# stoveguard.net
KiCad netlist of a schematic drawn in EAGLE
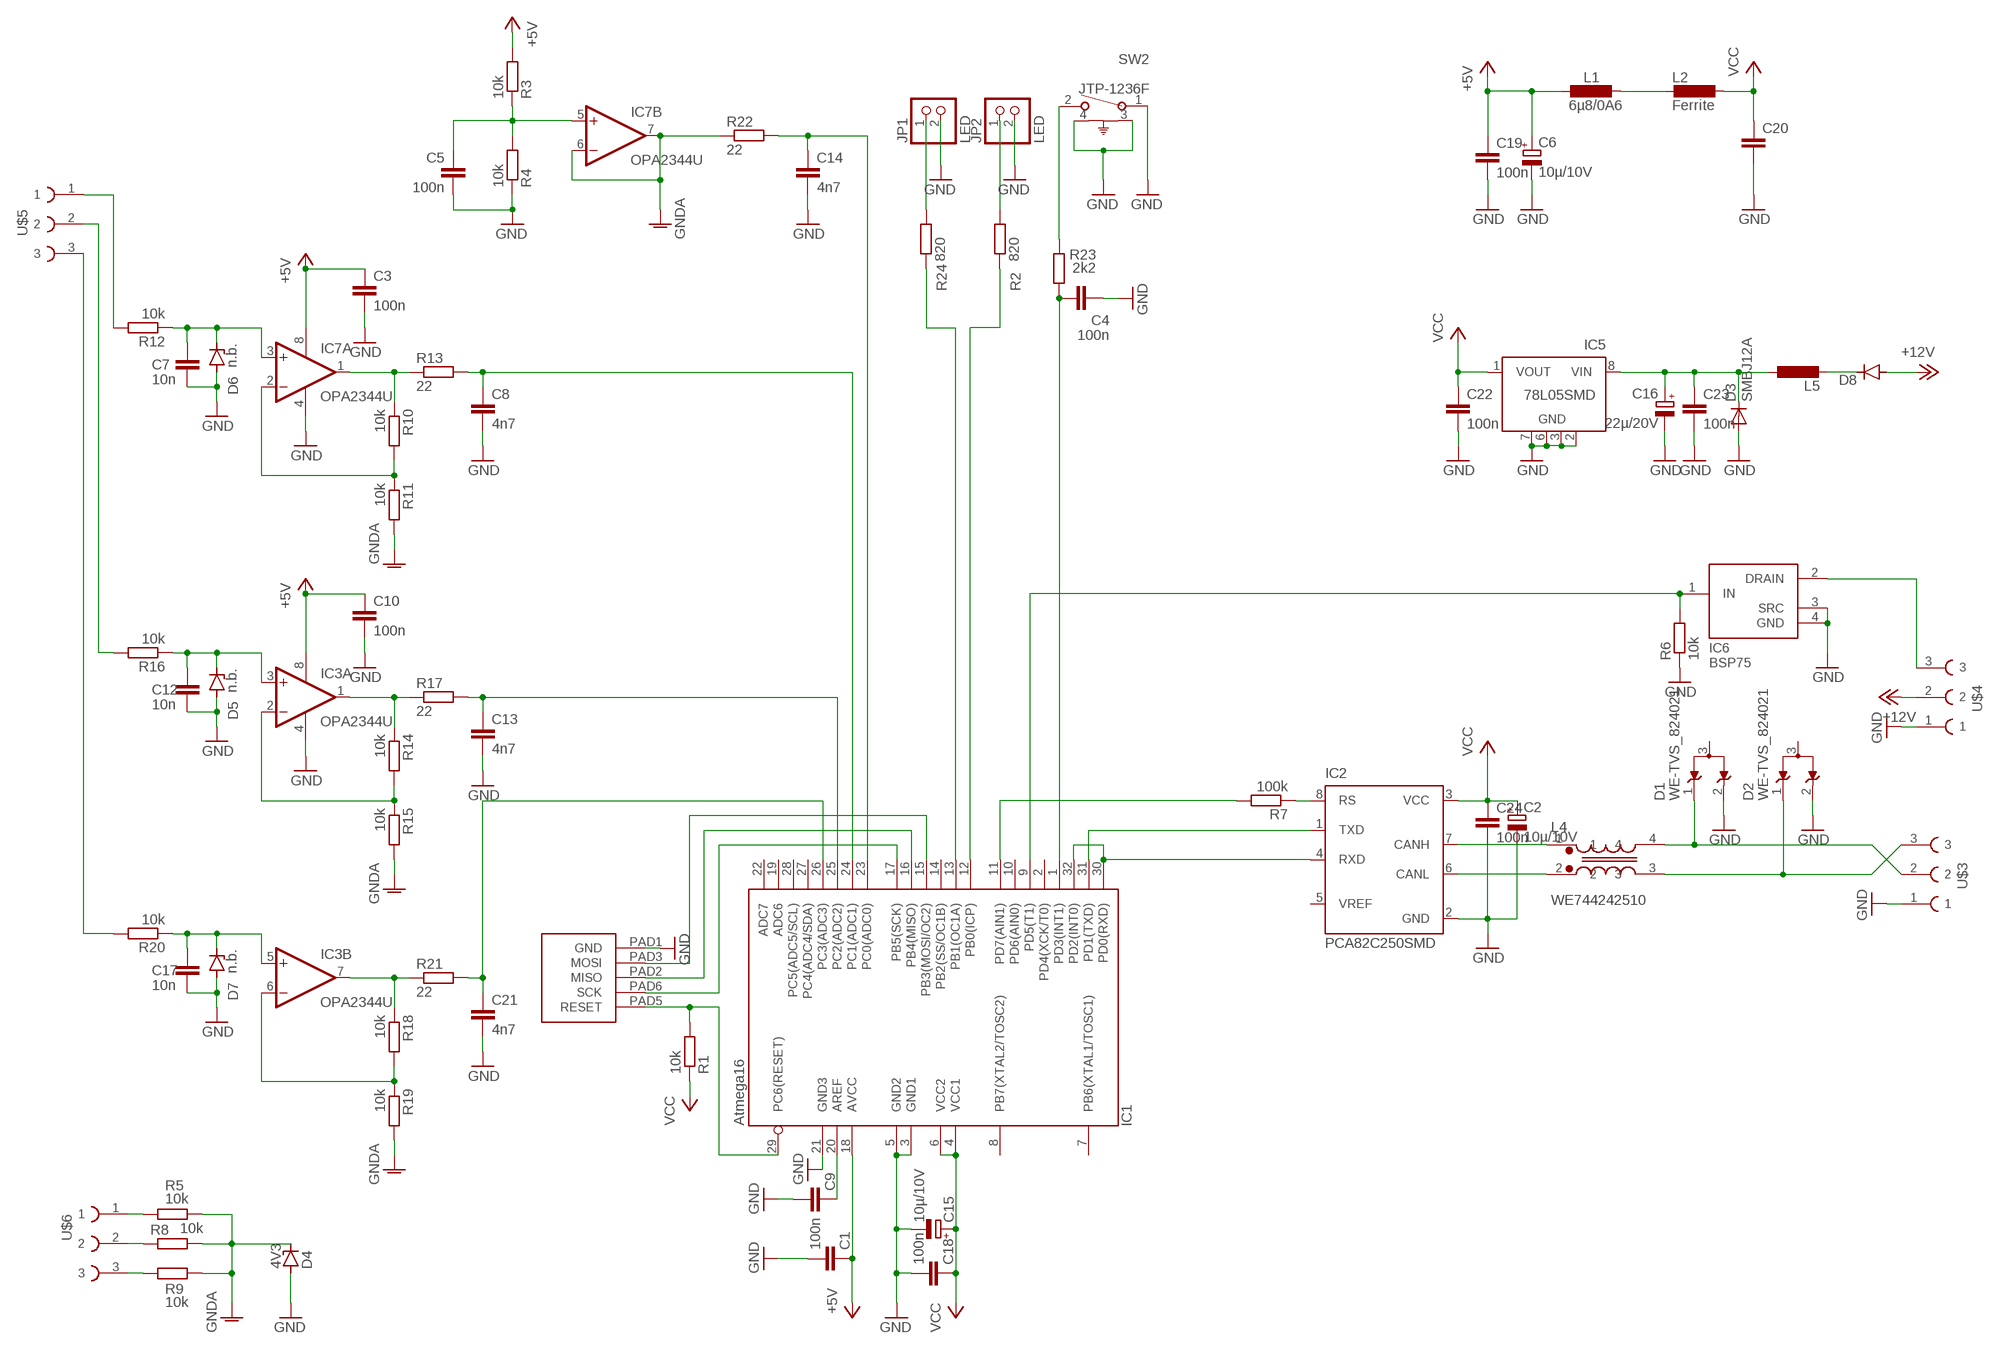
[diagram p0: schematic, sheet 1]

(export (version "E")
  (design (tool "Eeschema 10.0.6"))
  (components
    (comp (ref "C1")
      (value "100n")
      (footprint "eagle-import:C0603")
      (libsource (lib "eagle-import") (part "CC0603"))
    )
    (comp (ref "C2")
      (value "10µ/10V")
      (footprint "eagle-import:A_3216-18W")
      (libsource (lib "eagle-import") (part "CPOL-EUA/3216-18W"))
    )
    (comp (ref "C3")
      (value "100n")
      (footprint "eagle-import:C0603")
      (libsource (lib "eagle-import") (part "CC0603"))
    )
    (comp (ref "C4")
      (value "100n")
      (footprint "eagle-import:C0603")
      (libsource (lib "eagle-import") (part "CC0603"))
    )
    (comp (ref "C5")
      (value "100n")
      (footprint "eagle-import:C0603")
      (libsource (lib "eagle-import") (part "CC0603"))
    )
    (comp (ref "C6")
      (value "10µ/10V")
      (footprint "eagle-import:A_3216-18W")
      (libsource (lib "eagle-import") (part "CPOL-EUA/3216-18W"))
    )
    (comp (ref "C7")
      (value "10n")
      (footprint "eagle-import:C0603")
      (libsource (lib "eagle-import") (part "CC0603"))
    )
    (comp (ref "C8")
      (value "4n7")
      (footprint "eagle-import:C0603")
      (libsource (lib "eagle-import") (part "CC0603"))
    )
    (comp (ref "C9")
      (value "CC1206")
      (footprint "eagle-import:C1206")
      (libsource (lib "eagle-import") (part "CC1206"))
    )
    (comp (ref "C10")
      (value "100n")
      (footprint "eagle-import:C0603")
      (libsource (lib "eagle-import") (part "CC0603"))
    )
    (comp (ref "C12")
      (value "10n")
      (footprint "eagle-import:C0603")
      (libsource (lib "eagle-import") (part "CC0603"))
    )
    (comp (ref "C13")
      (value "4n7")
      (footprint "eagle-import:C0603")
      (libsource (lib "eagle-import") (part "CC0603"))
    )
    (comp (ref "C14")
      (value "4n7")
      (footprint "eagle-import:C0603")
      (libsource (lib "eagle-import") (part "CC0603"))
    )
    (comp (ref "C15")
      (value "10µ/10V")
      (footprint "eagle-import:A_3216-18W")
      (libsource (lib "eagle-import") (part "CPOL-EUA/3216-18W"))
    )
    (comp (ref "C16")
      (value "22µ/20V")
      (footprint "eagle-import:SMC_C")
      (libsource (lib "eagle-import") (part "CPOL-EUSMCC"))
    )
    (comp (ref "C17")
      (value "10n")
      (footprint "eagle-import:C0603")
      (libsource (lib "eagle-import") (part "CC0603"))
    )
    (comp (ref "C18")
      (value "100n")
      (footprint "eagle-import:C0603")
      (libsource (lib "eagle-import") (part "CC0603"))
    )
    (comp (ref "C19")
      (value "100n")
      (footprint "eagle-import:C0603")
      (libsource (lib "eagle-import") (part "CC0603"))
    )
    (comp (ref "C20")
      (value "CC0603")
      (footprint "eagle-import:C0603")
      (libsource (lib "eagle-import") (part "CC0603"))
    )
    (comp (ref "C21")
      (value "4n7")
      (footprint "eagle-import:C0603")
      (libsource (lib "eagle-import") (part "CC0603"))
    )
    (comp (ref "C22")
      (value "100n")
      (footprint "eagle-import:C0603")
      (libsource (lib "eagle-import") (part "CC0603"))
    )
    (comp (ref "C23")
      (value "100n")
      (footprint "eagle-import:C0603")
      (libsource (lib "eagle-import") (part "CC0603"))
    )
    (comp (ref "C24")
      (value "100n")
      (footprint "eagle-import:C0603")
      (libsource (lib "eagle-import") (part "CC0603"))
    )
    (comp (ref "D1")
      (value "WE-TVS_824021")
      (footprint "eagle-import:WE-TVS_SOT23-3L")
      (libsource (lib "eagle-import") (part "WE-TVS_824021"))
    )
    (comp (ref "D2")
      (value "WE-TVS_824021")
      (footprint "eagle-import:WE-TVS_SOT23-3L")
      (libsource (lib "eagle-import") (part "WE-TVS_824021"))
    )
    (comp (ref "D3")
      (value "SMBJ12A")
      (footprint "eagle-import:SMB")
      (libsource (lib "eagle-import") (part "DIODE-SMB"))
    )
    (comp (ref "D4")
      (value "4V3")
      (footprint "eagle-import:SOD80C")
      (libsource (lib "eagle-import") (part "ZENER-DIODESOD80C"))
    )
    (comp (ref "D5")
      (value "n.b.")
      (footprint "eagle-import:SOD80C")
      (libsource (lib "eagle-import") (part "ZENER-DIODESOD80C"))
    )
    (comp (ref "D6")
      (value "n.b.")
      (footprint "eagle-import:SOD80C")
      (libsource (lib "eagle-import") (part "ZENER-DIODESOD80C"))
    )
    (comp (ref "D7")
      (value "n.b.")
      (footprint "eagle-import:SOD80C")
      (libsource (lib "eagle-import") (part "ZENER-DIODESOD80C"))
    )
    (comp (ref "D8")
      (value "DIODE-MINIMELF")
      (footprint "eagle-import:MINIMELF")
      (libsource (lib "eagle-import") (part "diode_210_DIODE-MINIMELF"))
    )
    (comp (ref "IC1")
      (value "Atmega16")
      (footprint "eagle-import:TQFP32-08")
      (libsource (lib "eagle-import") (part "ATMEGA8"))
    )
    (comp (ref "IC2")
      (value "PCA82C250SMD")
      (footprint "eagle-import:SO8")
      (libsource (lib "eagle-import") (part "PCA82C250SMD"))
    )
    (comp (ref "IC3")
      (value "OPA2344U")
      (footprint "eagle-import:SO08")
      (libsource (lib "eagle-import") (part "OPA2U344"))
    )
    (comp (ref "IC5")
      (value "78L05SMD")
      (footprint "eagle-import:SO08")
      (libsource (lib "eagle-import") (part "78LSMD05"))
    )
    (comp (ref "IC6")
      (value "BSP75")
      (footprint "eagle-import:SOT223")
      (libsource (lib "eagle-import") (part "BSP75"))
    )
    (comp (ref "IC7")
      (value "OPA2344U")
      (footprint "eagle-import:SO08")
      (libsource (lib "eagle-import") (part "OPA2U344"))
    )
    (comp (ref "JP1")
      (value "LED")
      (footprint "eagle-import:1X02")
      (libsource (lib "eagle-import") (part "PINHD-1X2"))
    )
    (comp (ref "JP2")
      (value "LED")
      (footprint "eagle-import:1X02")
      (libsource (lib "eagle-import") (part "PINHD-1X2"))
    )
    (comp (ref "L1")
      (value "6µ8/0A6")
      (footprint "eagle-import:L1812")
      (libsource (lib "eagle-import") (part "rcl_L-EUL1812"))
    )
    (comp (ref "L2")
      (value "Ferrite")
      (footprint "eagle-import:L1806")
      (libsource (lib "eagle-import") (part "L-EUL1806"))
    )
    (comp (ref "L4")
      (value "WE744242510")
      (footprint "eagle-import:WE-SLM")
      (libsource (lib "eagle-import") (part "WE-SLM"))
    )
    (comp (ref "L5")
      (value "L-EUL1806")
      (footprint "eagle-import:L1806")
      (libsource (lib "eagle-import") (part "L-EUL1806"))
    )
    (comp (ref "R1")
      (value "10k")
      (footprint "eagle-import:R0603")
      (libsource (lib "eagle-import") (part "RR0603"))
    )
    (comp (ref "R2")
      (value "820")
      (footprint "eagle-import:R0603")
      (libsource (lib "eagle-import") (part "RR0603"))
    )
    (comp (ref "R3")
      (value "10k")
      (footprint "eagle-import:R0603")
      (libsource (lib "eagle-import") (part "RR0603"))
    )
    (comp (ref "R4")
      (value "10k")
      (footprint "eagle-import:R0603")
      (libsource (lib "eagle-import") (part "RR0603"))
    )
    (comp (ref "R5")
      (value "10k")
      (footprint "eagle-import:R0603")
      (libsource (lib "eagle-import") (part "RR0603"))
    )
    (comp (ref "R6")
      (value "10k")
      (footprint "eagle-import:R0603")
      (libsource (lib "eagle-import") (part "RR0603"))
    )
    (comp (ref "R7")
      (value "100k")
      (footprint "eagle-import:R0603")
      (libsource (lib "eagle-import") (part "RR0603"))
    )
    (comp (ref "R8")
      (value "10k")
      (footprint "eagle-import:R0603")
      (libsource (lib "eagle-import") (part "RR0603"))
    )
    (comp (ref "R9")
      (value "10k")
      (footprint "eagle-import:R0603")
      (libsource (lib "eagle-import") (part "RR0603"))
    )
    (comp (ref "R10")
      (value "10k")
      (footprint "eagle-import:R0603")
      (libsource (lib "eagle-import") (part "RR0603"))
    )
    (comp (ref "R11")
      (value "10k")
      (footprint "eagle-import:R0603")
      (libsource (lib "eagle-import") (part "RR0603"))
    )
    (comp (ref "R12")
      (value "10k")
      (footprint "eagle-import:R0603")
      (libsource (lib "eagle-import") (part "RR0603"))
    )
    (comp (ref "R13")
      (value "22")
      (footprint "eagle-import:R0603")
      (libsource (lib "eagle-import") (part "RR0603"))
    )
    (comp (ref "R14")
      (value "10k")
      (footprint "eagle-import:R0603")
      (libsource (lib "eagle-import") (part "RR0603"))
    )
    (comp (ref "R15")
      (value "10k")
      (footprint "eagle-import:R0603")
      (libsource (lib "eagle-import") (part "RR0603"))
    )
    (comp (ref "R16")
      (value "10k")
      (footprint "eagle-import:R0603")
      (libsource (lib "eagle-import") (part "RR0603"))
    )
    (comp (ref "R17")
      (value "22")
      (footprint "eagle-import:R0603")
      (libsource (lib "eagle-import") (part "RR0603"))
    )
    (comp (ref "R18")
      (value "10k")
      (footprint "eagle-import:R0603")
      (libsource (lib "eagle-import") (part "RR0603"))
    )
    (comp (ref "R19")
      (value "10k")
      (footprint "eagle-import:R0603")
      (libsource (lib "eagle-import") (part "RR0603"))
    )
    (comp (ref "R20")
      (value "10k")
      (footprint "eagle-import:R0603")
      (libsource (lib "eagle-import") (part "RR0603"))
    )
    (comp (ref "R21")
      (value "22")
      (footprint "eagle-import:R0603")
      (libsource (lib "eagle-import") (part "RR0603"))
    )
    (comp (ref "R22")
      (value "22")
      (footprint "eagle-import:R0603")
      (libsource (lib "eagle-import") (part "RR0603"))
    )
    (comp (ref "R23")
      (value "2k2")
      (footprint "eagle-import:R0603")
      (libsource (lib "eagle-import") (part "RR0603"))
    )
    (comp (ref "R24")
      (value "820")
      (footprint "eagle-import:R0603")
      (libsource (lib "eagle-import") (part "RR0603"))
    )
    (comp (ref "SW2")
      (value "JTP-1236F")
      (footprint "eagle-import:SW2_1825027-E")
      (fields
        (field (name "MANUFACTURER_PART_NUMBER") "1-1825027-4")
        (field (name "COPYRIGHT") "Copyright (C) 2016 Accelerated Designs. All rights reserved")
      )
      (libsource (lib "eagle-import") (part "1-1825027-4"))
    )
    (comp (ref "U$2")
      (value "ATMEL_ISP")
      (footprint "eagle-import:ATMEL_ISP")
      (libsource (lib "eagle-import") (part "ATMEL_ISP"))
    )
    (comp (ref "U$3")
      (value "MKDSO_2.5/3_L")
      (footprint "eagle-import:PHOENIX_MKDSO_2.5_3_L")
      (libsource (lib "eagle-import") (part "MKDSO_2.5/3_L"))
    )
    (comp (ref "U$4")
      (value "MKDSO_2.5/3_L")
      (footprint "eagle-import:PHOENIX_MKDSO_2.5_3_L")
      (libsource (lib "eagle-import") (part "MKDSO_2.5/3_L"))
    )
    (comp (ref "U$5")
      (value "MKDSO_2.5/3_R")
      (footprint "eagle-import:PHOENIX_MKDSO_2.5_3_R")
      (libsource (lib "eagle-import") (part "MKDSO_2.5/3_R"))
    )
    (comp (ref "U$6")
      (value "MKDSO_2.5/3_R")
      (footprint "eagle-import:PHOENIX_MKDSO_2.5_3_R")
      (libsource (lib "eagle-import") (part "MKDSO_2.5/3_R"))
    )
  )
  (nets
    (net (code "1") (name "+5V") (class "Default")
      (node (ref "C1") (pin "1") (pinfunction "1_1") (pintype "passive"))
      (node (ref "C10") (pin "1") (pinfunction "1_1") (pintype "passive"))
      (node (ref "C19") (pin "1") (pinfunction "1_1") (pintype "passive"))
      (node (ref "C3") (pin "1") (pinfunction "1_1") (pintype "passive"))
      (node (ref "C6") (pin "+") (pinfunction "+_+") (pintype "passive"))
      (node (ref "IC1") (pin "18") (pinfunction "AVCC_18") (pintype "power_in"))
      (node (ref "IC3") (pin "8") (pinfunction "V+_8") (pintype "power_in"))
      (node (ref "IC7") (pin "8") (pinfunction "V+_8") (pintype "power_in"))
      (node (ref "L1") (pin "2") (pinfunction "2_2") (pintype "passive"))
      (node (ref "R3") (pin "2") (pinfunction "2_2") (pintype "passive"))
    )
    (net (code "2") (name "+12V") (class "Default")
      (node (ref "D8") (pin "A") (pinfunction "A_A") (pintype "passive"))
      (node (ref "U$4") (pin "2") (pinfunction "2_2") (pintype "bidirectional"))
    )
    (net (code "3") (name "GND") (class "Default")
      (node (ref "C1") (pin "2") (pinfunction "2_2") (pintype "passive"))
      (node (ref "C10") (pin "2") (pinfunction "2_2") (pintype "passive"))
      (node (ref "C12") (pin "2") (pinfunction "2_2") (pintype "passive"))
      (node (ref "C13") (pin "2") (pinfunction "2_2") (pintype "passive"))
      (node (ref "C14") (pin "2") (pinfunction "2_2") (pintype "passive"))
      (node (ref "C15") (pin "-") (pinfunction "-_-") (pintype "passive"))
      (node (ref "C16") (pin "-") (pinfunction "-_-") (pintype "passive"))
      (node (ref "C17") (pin "2") (pinfunction "2_2") (pintype "passive"))
      (node (ref "C18") (pin "2") (pinfunction "2_2") (pintype "passive"))
      (node (ref "C19") (pin "2") (pinfunction "2_2") (pintype "passive"))
      (node (ref "C2") (pin "-") (pinfunction "-_-") (pintype "passive"))
      (node (ref "C20") (pin "2") (pinfunction "2_2") (pintype "passive"))
      (node (ref "C21") (pin "2") (pinfunction "2_2") (pintype "passive"))
      (node (ref "C22") (pin "2") (pinfunction "2_2") (pintype "passive"))
      (node (ref "C23") (pin "2") (pinfunction "2_2") (pintype "passive"))
      (node (ref "C24") (pin "2") (pinfunction "2_2") (pintype "passive"))
      (node (ref "C3") (pin "2") (pinfunction "2_2") (pintype "passive"))
      (node (ref "C4") (pin "1") (pinfunction "1_1") (pintype "passive"))
      (node (ref "C5") (pin "2") (pinfunction "2_2") (pintype "passive"))
      (node (ref "C6") (pin "-") (pinfunction "-_-") (pintype "passive"))
      (node (ref "C7") (pin "2") (pinfunction "2_2") (pintype "passive"))
      (node (ref "C8") (pin "2") (pinfunction "2_2") (pintype "passive"))
      (node (ref "C9") (pin "2") (pinfunction "2_2") (pintype "passive"))
      (node (ref "D1") (pin "2") (pinfunction "2_2") (pintype "passive"))
      (node (ref "D2") (pin "2") (pinfunction "2_2") (pintype "passive"))
      (node (ref "D3") (pin "A") (pinfunction "A_A") (pintype "passive"))
      (node (ref "D4") (pin "A") (pinfunction "A_A") (pintype "passive"))
      (node (ref "D5") (pin "A") (pinfunction "A_A") (pintype "passive"))
      (node (ref "D6") (pin "A") (pinfunction "A_A") (pintype "passive"))
      (node (ref "D7") (pin "A") (pinfunction "A_A") (pintype "passive"))
      (node (ref "IC1") (pin "21") (pinfunction "GND3_21") (pintype "power_in"))
      (node (ref "IC1") (pin "3") (pinfunction "GND1_3") (pintype "power_in"))
      (node (ref "IC1") (pin "5") (pinfunction "GND2_5") (pintype "power_in"))
      (node (ref "IC2") (pin "2") (pinfunction "GND_2") (pintype "power_in"))
      (node (ref "IC3") (pin "4") (pinfunction "V-_4") (pintype "power_in"))
      (node (ref "IC5") (pin "2") (pinfunction "GND_2") (pintype "power_in"))
      (node (ref "IC5") (pin "3") (pinfunction "GND_3") (pintype "power_in"))
      (node (ref "IC5") (pin "6") (pinfunction "GND_6") (pintype "power_in"))
      (node (ref "IC5") (pin "7") (pinfunction "GND_7") (pintype "power_in"))
      (node (ref "IC6") (pin "3") (pinfunction "SRC_3") (pintype "power_in"))
      (node (ref "IC6") (pin "4") (pinfunction "GND_4") (pintype "power_in"))
      (node (ref "IC7") (pin "4") (pinfunction "V-_4") (pintype "power_in"))
      (node (ref "JP1") (pin "2") (pinfunction "2_2") (pintype "passive"))
      (node (ref "JP2") (pin "2") (pinfunction "2_2") (pintype "passive"))
      (node (ref "R4") (pin "1") (pinfunction "1_1") (pintype "passive"))
      (node (ref "R6") (pin "1") (pinfunction "1_1") (pintype "passive"))
      (node (ref "SW2") (pin "1") (pinfunction "1_1") (pintype "passive"))
      (node (ref "SW2") (pin "3") (pinfunction "3_3") (pintype "passive"))
      (node (ref "SW2") (pin "4") (pinfunction "4_4") (pintype "passive"))
      (node (ref "U$2") (pin "PAD1") (pinfunction "GND_PAD1") (pintype "power_in"))
      (node (ref "U$3") (pin "1") (pinfunction "1_1") (pintype "bidirectional"))
      (node (ref "U$4") (pin "1") (pinfunction "1_1") (pintype "bidirectional"))
    )
    (net (code "4") (name "GNDA") (class "Default")
      (node (ref "D4") (pin "C") (pinfunction "C_C") (pintype "passive"))
      (node (ref "IC7") (pin "6") (pinfunction "-IN_6") (pintype "input"))
      (node (ref "IC7") (pin "7") (pinfunction "OUT_7") (pintype "output"))
      (node (ref "R11") (pin "2") (pinfunction "2_2") (pintype "passive"))
      (node (ref "R15") (pin "2") (pinfunction "2_2") (pintype "passive"))
      (node (ref "R19") (pin "2") (pinfunction "2_2") (pintype "passive"))
      (node (ref "R22") (pin "1") (pinfunction "1_1") (pintype "passive"))
      (node (ref "R5") (pin "1") (pinfunction "1_1") (pintype "passive"))
      (node (ref "R8") (pin "1") (pinfunction "1_1") (pintype "passive"))
      (node (ref "R9") (pin "1") (pinfunction "1_1") (pintype "passive"))
    )
    (net (code "5") (name "Net-(D1-Pad1)") (class "Default")
      (node (ref "D1") (pin "1") (pinfunction "1_1") (pintype "passive"))
      (node (ref "L4") (pin "4") (pinfunction "4_4") (pintype "bidirectional"))
      (node (ref "U$3") (pin "2") (pinfunction "2_2") (pintype "bidirectional"))
    )
    (net (code "6") (name "Net-(D2-Pad1)") (class "Default")
      (node (ref "D2") (pin "1") (pinfunction "1_1") (pintype "passive"))
      (node (ref "L4") (pin "3") (pinfunction "3_3") (pintype "bidirectional"))
      (node (ref "U$3") (pin "3") (pinfunction "3_3") (pintype "bidirectional"))
    )
    (net (code "7") (name "Net-(D8-PadC)") (class "Default")
      (node (ref "D8") (pin "C") (pinfunction "C_C") (pintype "passive"))
      (node (ref "L5") (pin "2") (pinfunction "2_2") (pintype "passive"))
    )
    (net (code "8") (name "Net-(IC1-AREF)") (class "Default")
      (node (ref "C9") (pin "1") (pinfunction "1_1") (pintype "passive"))
      (node (ref "IC1") (pin "20") (pinfunction "AREF_20") (pintype "power_in"))
    )
    (net (code "9") (name "Net-(IC1-PB0(ICP))") (class "Default")
      (node (ref "IC1") (pin "12") (pinfunction "PB0(ICP)_12") (pintype "bidirectional"))
      (node (ref "R2") (pin "1") (pinfunction "1_1") (pintype "passive"))
    )
    (net (code "10") (name "Net-(IC1-PB1(OC1A))") (class "Default")
      (node (ref "IC1") (pin "13") (pinfunction "PB1(OC1A)_13") (pintype "bidirectional"))
      (node (ref "R24") (pin "1") (pinfunction "1_1") (pintype "passive"))
    )
    (net (code "11") (name "Net-(IC1-PB3(MOSI{slash}OC2))") (class "Default")
      (node (ref "IC1") (pin "15") (pinfunction "PB3(MOSI/OC2)_15") (pintype "bidirectional"))
      (node (ref "U$2") (pin "PAD3") (pinfunction "MOSI_PAD3") (pintype "bidirectional"))
    )
    (net (code "12") (name "Net-(IC1-PB4(MISO))") (class "Default")
      (node (ref "IC1") (pin "16") (pinfunction "PB4(MISO)_16") (pintype "bidirectional"))
      (node (ref "U$2") (pin "PAD2") (pinfunction "MISO_PAD2") (pintype "bidirectional"))
    )
    (net (code "13") (name "Net-(IC1-PB5(SCK))") (class "Default")
      (node (ref "IC1") (pin "17") (pinfunction "PB5(SCK)_17") (pintype "bidirectional"))
      (node (ref "U$2") (pin "PAD6") (pinfunction "SCK_PAD6") (pintype "bidirectional"))
    )
    (net (code "14") (name "Net-(IC1-PC0(ADC0))") (class "Default")
      (node (ref "C14") (pin "1") (pinfunction "1_1") (pintype "passive"))
      (node (ref "IC1") (pin "23") (pinfunction "PC0(ADC0)_23") (pintype "bidirectional"))
      (node (ref "R22") (pin "2") (pinfunction "2_2") (pintype "passive"))
    )
    (net (code "15") (name "Net-(IC1-PC1(ADC1))") (class "Default")
      (node (ref "C8") (pin "1") (pinfunction "1_1") (pintype "passive"))
      (node (ref "IC1") (pin "24") (pinfunction "PC1(ADC1)_24") (pintype "bidirectional"))
      (node (ref "R13") (pin "2") (pinfunction "2_2") (pintype "passive"))
    )
    (net (code "16") (name "Net-(IC1-PC2(ADC2))") (class "Default")
      (node (ref "C13") (pin "1") (pinfunction "1_1") (pintype "passive"))
      (node (ref "IC1") (pin "25") (pinfunction "PC2(ADC2)_25") (pintype "bidirectional"))
      (node (ref "R17") (pin "2") (pinfunction "2_2") (pintype "passive"))
    )
    (net (code "17") (name "Net-(IC1-PC3(ADC3))") (class "Default")
      (node (ref "C21") (pin "1") (pinfunction "1_1") (pintype "passive"))
      (node (ref "IC1") (pin "26") (pinfunction "PC3(ADC3)_26") (pintype "bidirectional"))
      (node (ref "R21") (pin "2") (pinfunction "2_2") (pintype "passive"))
    )
    (net (code "18") (name "Net-(IC1-PC6(RESET))") (class "Default")
      (node (ref "IC1") (pin "29") (pinfunction "PC6(RESET)_29") (pintype "bidirectional"))
      (node (ref "R1") (pin "2") (pinfunction "2_2") (pintype "passive"))
      (node (ref "U$2") (pin "PAD5") (pinfunction "RESET_PAD5") (pintype "bidirectional"))
    )
    (net (code "19") (name "Net-(IC1-PD0(RXD))") (class "Default")
      (node (ref "IC1") (pin "30") (pinfunction "PD0(RXD)_30") (pintype "bidirectional"))
      (node (ref "IC1") (pin "32") (pinfunction "PD2(INT0)_32") (pintype "bidirectional"))
      (node (ref "IC2") (pin "4") (pinfunction "RXD_4") (pintype "output"))
    )
    (net (code "20") (name "Net-(IC1-PD1(TXD))") (class "Default")
      (node (ref "IC1") (pin "31") (pinfunction "PD1(TXD)_31") (pintype "bidirectional"))
      (node (ref "IC2") (pin "1") (pinfunction "TXD_1") (pintype "input"))
    )
    (net (code "21") (name "Net-(IC1-PD3(INT1))") (class "Default")
      (node (ref "C4") (pin "2") (pinfunction "2_2") (pintype "passive"))
      (node (ref "IC1") (pin "1") (pinfunction "PD3(INT1)_1") (pintype "bidirectional"))
      (node (ref "R23") (pin "2") (pinfunction "2_2") (pintype "passive"))
    )
    (net (code "22") (name "Net-(IC1-PD5(T1))") (class "Default")
      (node (ref "IC1") (pin "9") (pinfunction "PD5(T1)_9") (pintype "bidirectional"))
      (node (ref "IC6") (pin "1") (pinfunction "IN_1") (pintype "input"))
      (node (ref "R6") (pin "2") (pinfunction "2_2") (pintype "passive"))
    )
    (net (code "23") (name "Net-(IC1-PD7(AIN1))") (class "Default")
      (node (ref "IC1") (pin "11") (pinfunction "PD7(AIN1)_11") (pintype "bidirectional"))
      (node (ref "R7") (pin "2") (pinfunction "2_2") (pintype "passive"))
    )
    (net (code "24") (name "Net-(IC2-CANH)") (class "Default")
      (node (ref "IC2") (pin "7") (pinfunction "CANH_7") (pintype "bidirectional"))
      (node (ref "L4") (pin "1") (pinfunction "1_1") (pintype "bidirectional"))
    )
    (net (code "25") (name "Net-(IC2-CANL)") (class "Default")
      (node (ref "IC2") (pin "6") (pinfunction "CANL_6") (pintype "bidirectional"))
      (node (ref "L4") (pin "2") (pinfunction "2_2") (pintype "bidirectional"))
    )
    (net (code "26") (name "Net-(IC2-RS)") (class "Default")
      (node (ref "IC2") (pin "8") (pinfunction "RS_8") (pintype "input"))
      (node (ref "R7") (pin "1") (pinfunction "1_1") (pintype "passive"))
    )
    (net (code "27") (name "Net-(IC3A-+IN)") (class "Default")
      (node (ref "C12") (pin "1") (pinfunction "1_1") (pintype "passive"))
      (node (ref "D5") (pin "C") (pinfunction "C_C") (pintype "passive"))
      (node (ref "IC3") (pin "3") (pinfunction "+IN_3") (pintype "input"))
      (node (ref "R16") (pin "1") (pinfunction "1_1") (pintype "passive"))
    )
    (net (code "28") (name "Net-(IC3A--IN)") (class "Default")
      (node (ref "IC3") (pin "2") (pinfunction "-IN_2") (pintype "input"))
      (node (ref "R14") (pin "2") (pinfunction "2_2") (pintype "passive"))
      (node (ref "R15") (pin "1") (pinfunction "1_1") (pintype "passive"))
    )
    (net (code "29") (name "Net-(IC3A-OUT)") (class "Default")
      (node (ref "IC3") (pin "1") (pinfunction "OUT_1") (pintype "output"))
      (node (ref "R14") (pin "1") (pinfunction "1_1") (pintype "passive"))
      (node (ref "R17") (pin "1") (pinfunction "1_1") (pintype "passive"))
    )
    (net (code "30") (name "Net-(IC3B-+IN)") (class "Default")
      (node (ref "C17") (pin "1") (pinfunction "1_1") (pintype "passive"))
      (node (ref "D7") (pin "C") (pinfunction "C_C") (pintype "passive"))
      (node (ref "IC3") (pin "5") (pinfunction "+IN_5") (pintype "input"))
      (node (ref "R20") (pin "1") (pinfunction "1_1") (pintype "passive"))
    )
    (net (code "31") (name "Net-(IC3B--IN)") (class "Default")
      (node (ref "IC3") (pin "6") (pinfunction "-IN_6") (pintype "input"))
      (node (ref "R18") (pin "2") (pinfunction "2_2") (pintype "passive"))
      (node (ref "R19") (pin "1") (pinfunction "1_1") (pintype "passive"))
    )
    (net (code "32") (name "Net-(IC3B-OUT)") (class "Default")
      (node (ref "IC3") (pin "7") (pinfunction "OUT_7") (pintype "output"))
      (node (ref "R18") (pin "1") (pinfunction "1_1") (pintype "passive"))
      (node (ref "R21") (pin "1") (pinfunction "1_1") (pintype "passive"))
    )
    (net (code "33") (name "Net-(IC5A-VIN)") (class "Default")
      (node (ref "C16") (pin "+") (pinfunction "+_+") (pintype "passive"))
      (node (ref "C23") (pin "1") (pinfunction "1_1") (pintype "passive"))
      (node (ref "D3") (pin "C") (pinfunction "C_C") (pintype "passive"))
      (node (ref "IC5") (pin "8") (pinfunction "VIN_8") (pintype "passive"))
      (node (ref "L5") (pin "1") (pinfunction "1_1") (pintype "passive"))
    )
    (net (code "34") (name "Net-(IC6-DRAIN)") (class "Default")
      (node (ref "IC6") (pin "2") (pinfunction "DRAIN_2") (pintype "output"))
      (node (ref "U$4") (pin "3") (pinfunction "3_3") (pintype "bidirectional"))
    )
    (net (code "35") (name "Net-(IC7A-+IN)") (class "Default")
      (node (ref "C7") (pin "1") (pinfunction "1_1") (pintype "passive"))
      (node (ref "D6") (pin "C") (pinfunction "C_C") (pintype "passive"))
      (node (ref "IC7") (pin "3") (pinfunction "+IN_3") (pintype "input"))
      (node (ref "R12") (pin "1") (pinfunction "1_1") (pintype "passive"))
    )
    (net (code "36") (name "Net-(IC7A--IN)") (class "Default")
      (node (ref "IC7") (pin "2") (pinfunction "-IN_2") (pintype "input"))
      (node (ref "R10") (pin "2") (pinfunction "2_2") (pintype "passive"))
      (node (ref "R11") (pin "1") (pinfunction "1_1") (pintype "passive"))
    )
    (net (code "37") (name "Net-(IC7A-OUT)") (class "Default")
      (node (ref "IC7") (pin "1") (pinfunction "OUT_1") (pintype "output"))
      (node (ref "R10") (pin "1") (pinfunction "1_1") (pintype "passive"))
      (node (ref "R13") (pin "1") (pinfunction "1_1") (pintype "passive"))
    )
    (net (code "38") (name "Net-(IC7B-+IN)") (class "Default")
      (node (ref "C5") (pin "1") (pinfunction "1_1") (pintype "passive"))
      (node (ref "IC7") (pin "5") (pinfunction "+IN_5") (pintype "input"))
      (node (ref "R3") (pin "1") (pinfunction "1_1") (pintype "passive"))
      (node (ref "R4") (pin "2") (pinfunction "2_2") (pintype "passive"))
    )
    (net (code "39") (name "Net-(JP1-Pad1)") (class "Default")
      (node (ref "JP1") (pin "1") (pinfunction "1_1") (pintype "passive"))
      (node (ref "R24") (pin "2") (pinfunction "2_2") (pintype "passive"))
    )
    (net (code "40") (name "Net-(JP2-Pad1)") (class "Default")
      (node (ref "JP2") (pin "1") (pinfunction "1_1") (pintype "passive"))
      (node (ref "R2") (pin "2") (pinfunction "2_2") (pintype "passive"))
    )
    (net (code "41") (name "Net-(L1-Pad1)") (class "Default")
      (node (ref "L1") (pin "1") (pinfunction "1_1") (pintype "passive"))
      (node (ref "L2") (pin "2") (pinfunction "2_2") (pintype "passive"))
    )
    (net (code "42") (name "Net-(R5-Pad2)") (class "Default")
      (node (ref "R5") (pin "2") (pinfunction "2_2") (pintype "passive"))
      (node (ref "U$6") (pin "1") (pinfunction "1_1") (pintype "bidirectional"))
    )
    (net (code "43") (name "Net-(R8-Pad2)") (class "Default")
      (node (ref "R8") (pin "2") (pinfunction "2_2") (pintype "passive"))
      (node (ref "U$6") (pin "2") (pinfunction "2_2") (pintype "bidirectional"))
    )
    (net (code "44") (name "Net-(R9-Pad2)") (class "Default")
      (node (ref "R9") (pin "2") (pinfunction "2_2") (pintype "passive"))
      (node (ref "U$6") (pin "3") (pinfunction "3_3") (pintype "bidirectional"))
    )
    (net (code "45") (name "Net-(R12-Pad2)") (class "Default")
      (node (ref "R12") (pin "2") (pinfunction "2_2") (pintype "passive"))
      (node (ref "U$5") (pin "1") (pinfunction "1_1") (pintype "bidirectional"))
    )
    (net (code "46") (name "Net-(R16-Pad2)") (class "Default")
      (node (ref "R16") (pin "2") (pinfunction "2_2") (pintype "passive"))
      (node (ref "U$5") (pin "2") (pinfunction "2_2") (pintype "bidirectional"))
    )
    (net (code "47") (name "Net-(R20-Pad2)") (class "Default")
      (node (ref "R20") (pin "2") (pinfunction "2_2") (pintype "passive"))
      (node (ref "U$5") (pin "3") (pinfunction "3_3") (pintype "bidirectional"))
    )
    (net (code "48") (name "Net-(R23-Pad1)") (class "Default")
      (node (ref "R23") (pin "1") (pinfunction "1_1") (pintype "passive"))
      (node (ref "SW2") (pin "2") (pinfunction "2_2") (pintype "passive"))
    )
    (net (code "49") (name "VCC") (class "Default")
      (node (ref "C15") (pin "+") (pinfunction "+_+") (pintype "passive"))
      (node (ref "C18") (pin "1") (pinfunction "1_1") (pintype "passive"))
      (node (ref "C2") (pin "+") (pinfunction "+_+") (pintype "passive"))
      (node (ref "C20") (pin "1") (pinfunction "1_1") (pintype "passive"))
      (node (ref "C22") (pin "1") (pinfunction "1_1") (pintype "passive"))
      (node (ref "C24") (pin "1") (pinfunction "1_1") (pintype "passive"))
      (node (ref "IC1") (pin "4") (pinfunction "VCC1_4") (pintype "power_in"))
      (node (ref "IC1") (pin "6") (pinfunction "VCC2_6") (pintype "power_in"))
      (node (ref "IC2") (pin "3") (pinfunction "VCC_3") (pintype "power_in"))
      (node (ref "IC5") (pin "1") (pinfunction "VOUT_1") (pintype "output"))
      (node (ref "L2") (pin "1") (pinfunction "1_1") (pintype "passive"))
      (node (ref "R1") (pin "1") (pinfunction "1_1") (pintype "passive"))
    )
    (net (code "50") (name "unconnected-(D1-GND-Pad3)") (class "Default")
      (node (ref "D1") (pin "3") (pinfunction "GND_3") (pintype "passive"))
    )
    (net (code "51") (name "unconnected-(D2-GND-Pad3)") (class "Default")
      (node (ref "D2") (pin "3") (pinfunction "GND_3") (pintype "passive"))
    )
    (net (code "52") (name "unconnected-(IC1-ADC6-Pad19)") (class "Default")
      (node (ref "IC1") (pin "19") (pinfunction "ADC6_19") (pintype "bidirectional"))
    )
    (net (code "53") (name "unconnected-(IC1-ADC7-Pad22)") (class "Default")
      (node (ref "IC1") (pin "22") (pinfunction "ADC7_22") (pintype "bidirectional"))
    )
    (net (code "54") (name "unconnected-(IC1-PB2(SS{slash}OC1B)-Pad14)") (class "Default")
      (node (ref "IC1") (pin "14") (pinfunction "PB2(SS/OC1B)_14") (pintype "bidirectional"))
    )
    (net (code "55") (name "unconnected-(IC1-PB6(XTAL1{slash}TOSC1)-Pad7)") (class "Default")
      (node (ref "IC1") (pin "7") (pinfunction "PB6(XTAL1/TOSC1)_7") (pintype "bidirectional"))
    )
    (net (code "56") (name "unconnected-(IC1-PB7(XTAL2{slash}TOSC2)-Pad8)") (class "Default")
      (node (ref "IC1") (pin "8") (pinfunction "PB7(XTAL2/TOSC2)_8") (pintype "bidirectional"))
    )
    (net (code "57") (name "unconnected-(IC1-PC4(ADC4{slash}SDA)-Pad27)") (class "Default")
      (node (ref "IC1") (pin "27") (pinfunction "PC4(ADC4/SDA)_27") (pintype "bidirectional"))
    )
    (net (code "58") (name "unconnected-(IC1-PC5(ADC5{slash}SCL)-Pad28)") (class "Default")
      (node (ref "IC1") (pin "28") (pinfunction "PC5(ADC5/SCL)_28") (pintype "bidirectional"))
    )
    (net (code "59") (name "unconnected-(IC1-PD4(XCK{slash}T0)-Pad2)") (class "Default")
      (node (ref "IC1") (pin "2") (pinfunction "PD4(XCK/T0)_2") (pintype "bidirectional"))
    )
    (net (code "60") (name "unconnected-(IC1-PD6(AIN0)-Pad10)") (class "Default")
      (node (ref "IC1") (pin "10") (pinfunction "PD6(AIN0)_10") (pintype "bidirectional"))
    )
    (net (code "61") (name "unconnected-(IC2-VREF-Pad5)") (class "Default")
      (node (ref "IC2") (pin "5") (pinfunction "VREF_5") (pintype "output"))
    )
  )
)
